# jayday_fez40_5v.net
KiCad netlist of a schematic drawn in EAGLE
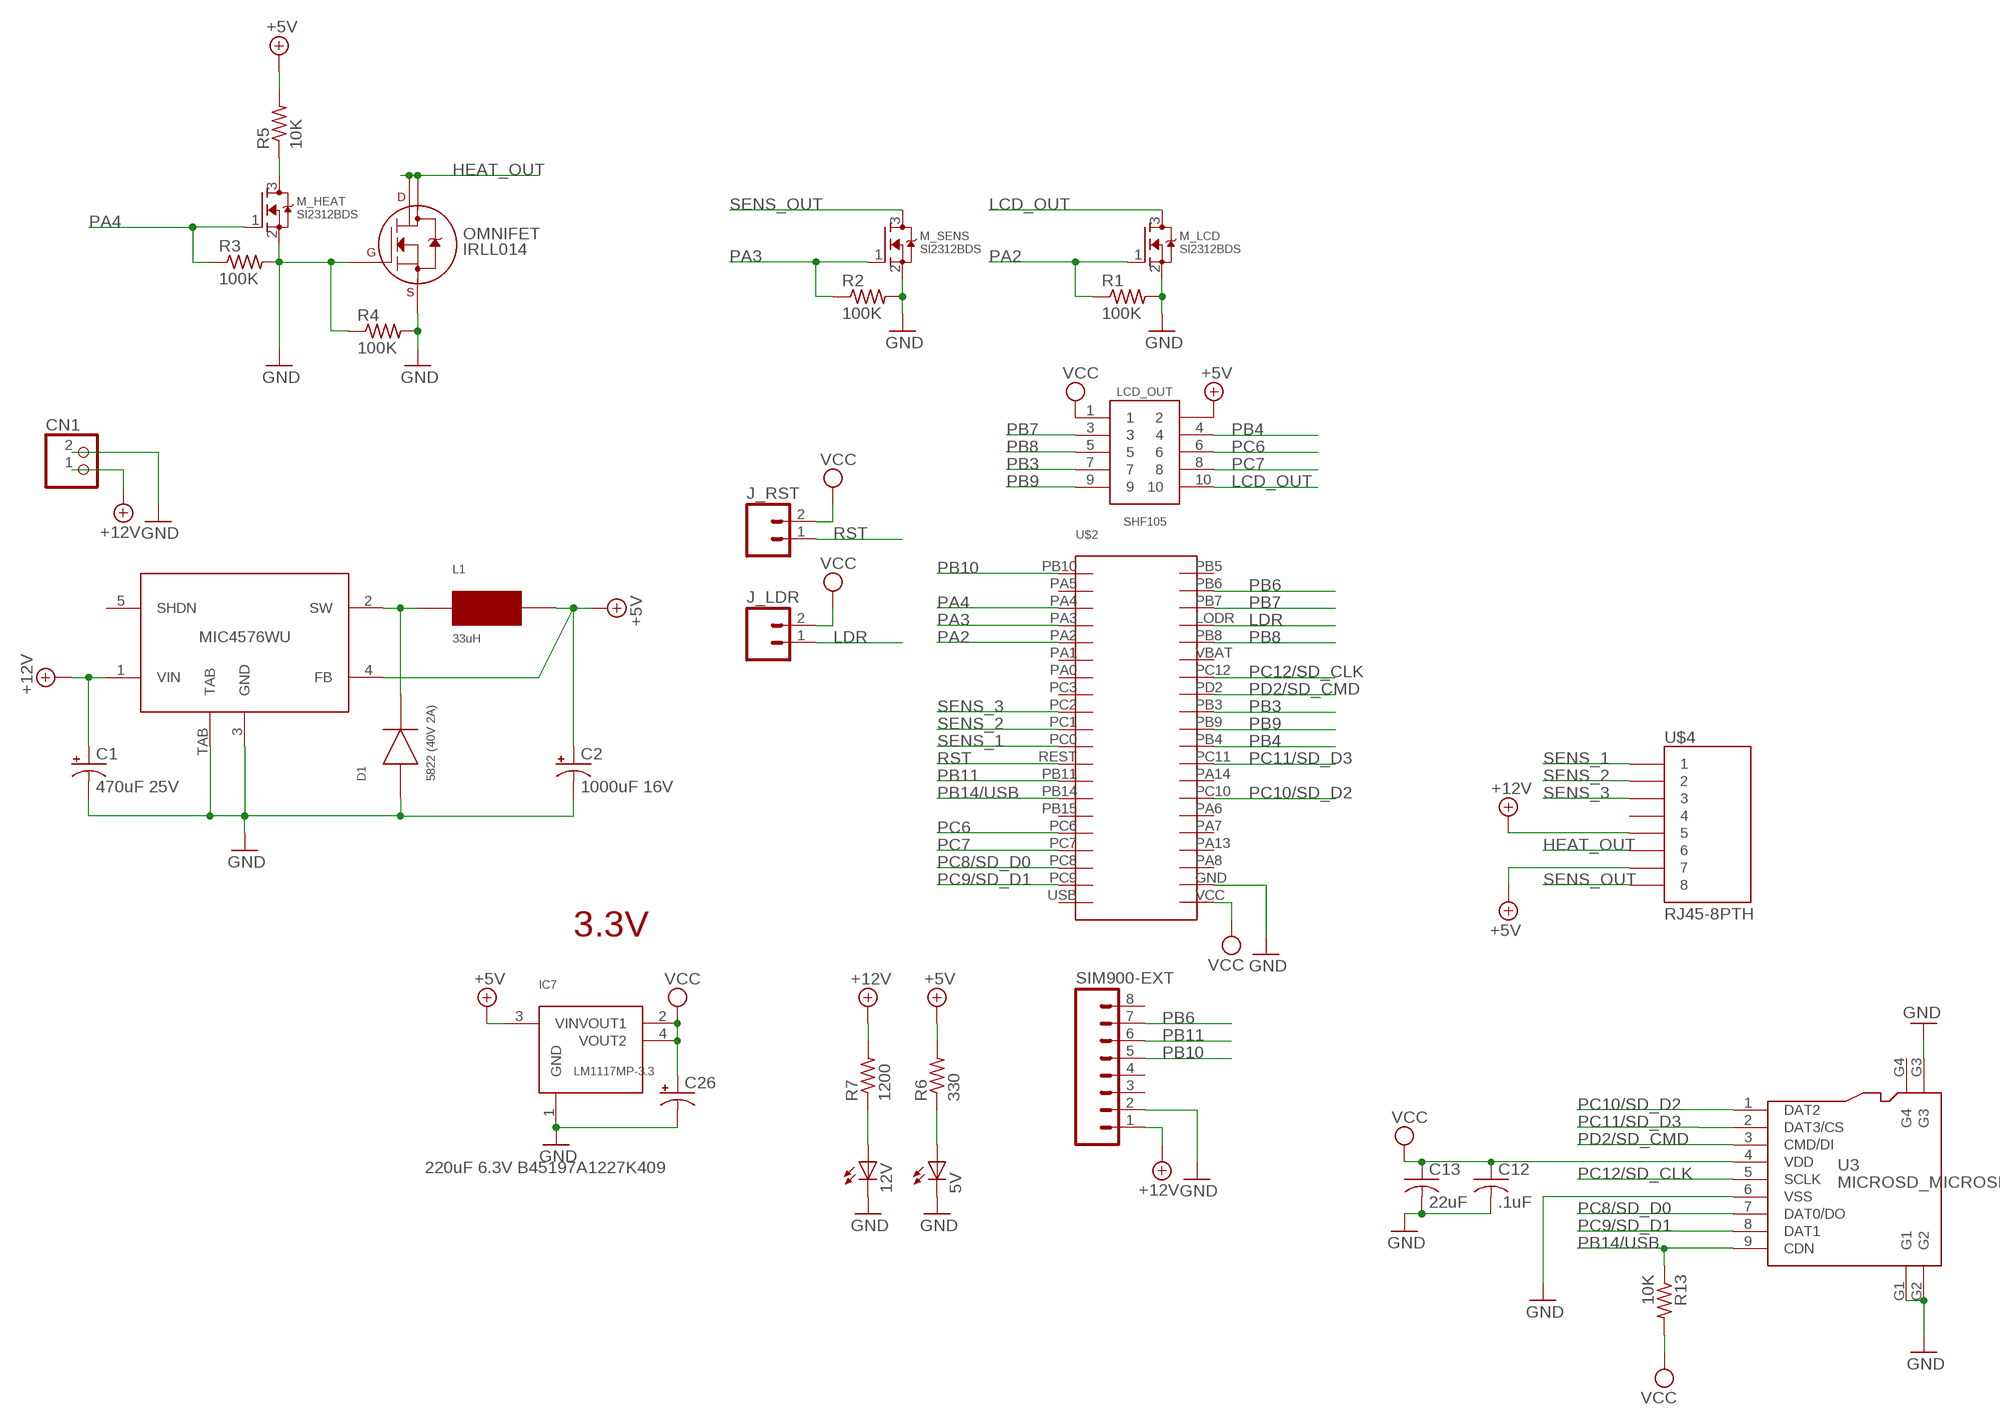
[diagram p0: schematic, sheet 1]

(export (version "E")
  (design (tool "Eeschema 10.0.6"))
  (components
    (comp (ref "5V")
      (value "LEDCHIPLED_0805")
      (footprint "eagle-import:CHIPLED_0805")
      (libsource (lib "eagle-import") (part "LEDCHIPLED_0805"))
    )
    (comp (ref "12V")
      (value "LEDCHIPLED_0805")
      (footprint "eagle-import:CHIPLED_0805")
      (libsource (lib "eagle-import") (part "LEDCHIPLED_0805"))
    )
    (comp (ref "C1")
      (value "470uF 25V")
      (footprint "eagle-import:PANASONIC_E")
      (libsource (lib "eagle-import") (part "CAP_POLE"))
    )
    (comp (ref "C2")
      (value "1000uF 16V")
      (footprint "eagle-import:PANASONIC_E")
      (libsource (lib "eagle-import") (part "CAP_POLE"))
    )
    (comp (ref "C12")
      (value ".1uF")
      (footprint "eagle-import:C0603K")
      (libsource (lib "eagle-import") (part "C-USC0603K"))
    )
    (comp (ref "C13")
      (value "22uF")
      (footprint "eagle-import:C0805K")
      (libsource (lib "eagle-import") (part "C-USC0805K"))
    )
    (comp (ref "C26")
      (value "220uF 6.3V B45197A1227K409")
      (footprint "eagle-import:D_7343-31W")
      (libsource (lib "eagle-import") (part "CPOL-USD/7343-31W"))
    )
    (comp (ref "CN1")
      (value "JST_2PIN-THM-RA")
      (footprint "eagle-import:JST-PH-2-THM-RA")
      (libsource (lib "eagle-import") (part "JST_2PIN-THM-RA"))
    )
    (comp (ref "D1")
      (value "5822 (40V 2A)")
      (footprint "eagle-import:GHI_DIODE_SMA")
      (libsource (lib "eagle-import") (part "GHI_DIODE_SMA"))
    )
    (comp (ref "IC7")
      (value "LM1117MP-3.3")
      (footprint "eagle-import:SOT223")
      (libsource (lib "eagle-import") (part "LM1117"))
    )
    (comp (ref "J_LDR")
      (value "M02PTH")
      (footprint "eagle-import:1X02")
      (libsource (lib "eagle-import") (part "M02PTH"))
    )
    (comp (ref "J_RST")
      (value "M02PTH")
      (footprint "eagle-import:1X02")
      (libsource (lib "eagle-import") (part "M02PTH"))
    )
    (comp (ref "L1")
      (value "33uH")
      (footprint "eagle-import:GHI_UP2BXXX")
      (libsource (lib "eagle-import") (part "GHI_UP2BXXX"))
    )
    (comp (ref "LCD_OUT")
      (value "SHF105")
      (footprint "eagle-import:GAD_PAC_SMD")
      (libsource (lib "eagle-import") (part "SHF105"))
    )
    (comp (ref "M_HEAT")
      (value "SI2312BDS")
      (footprint "eagle-import:TO-236")
      (libsource (lib "eagle-import") (part "SI2312BDS"))
    )
    (comp (ref "M_LCD")
      (value "SI2312BDS")
      (footprint "eagle-import:TO-236")
      (libsource (lib "eagle-import") (part "SI2312BDS"))
    )
    (comp (ref "M_SENS")
      (value "SI2312BDS")
      (footprint "eagle-import:TO-236")
      (libsource (lib "eagle-import") (part "SI2312BDS"))
    )
    (comp (ref "OMNIFET")
      (value "IRLL014")
      (footprint "eagle-import:SOT-223")
      (libsource (lib "eagle-import") (part "IRLL014"))
    )
    (comp (ref "R1")
      (value "100K")
      (footprint "eagle-import:R0603")
      (libsource (lib "eagle-import") (part "R-US_R0603"))
    )
    (comp (ref "R2")
      (value "100K")
      (footprint "eagle-import:R0603")
      (libsource (lib "eagle-import") (part "R-US_R0603"))
    )
    (comp (ref "R3")
      (value "100K")
      (footprint "eagle-import:R0603")
      (libsource (lib "eagle-import") (part "R-US_R0603"))
    )
    (comp (ref "R4")
      (value "100K")
      (footprint "eagle-import:R0603")
      (libsource (lib "eagle-import") (part "R-US_R0603"))
    )
    (comp (ref "R5")
      (value "10K")
      (footprint "eagle-import:R0603")
      (libsource (lib "eagle-import") (part "R-US_R0603"))
    )
    (comp (ref "R6")
      (value "330")
      (footprint "eagle-import:R0603")
      (libsource (lib "eagle-import") (part "rcl_R-US_R0603"))
    )
    (comp (ref "R7")
      (value "1200")
      (footprint "eagle-import:R0603")
      (libsource (lib "eagle-import") (part "rcl_R-US_R0603"))
    )
    (comp (ref "R13")
      (value "10K")
      (footprint "eagle-import:R0603")
      (libsource (lib "eagle-import") (part "rcl_R-US_R0603"))
    )
    (comp (ref "SIM900-EXT")
      (value "M081X08")
      (footprint "eagle-import:1X08")
      (libsource (lib "eagle-import") (part "M081X08"))
    )
    (comp (ref "U$1")
      (value "MIC4576WU")
      (footprint "eagle-import:TO263-5")
      (libsource (lib "eagle-import") (part "MIC4576WU"))
    )
    (comp (ref "U$2")
      (value "FEZ_CERB_40")
      (footprint "eagle-import:FEZ_CERB_40")
      (libsource (lib "eagle-import") (part "FEZ_CERB_40"))
    )
    (comp (ref "U$4")
      (value "RJ45-8PTH")
      (footprint "eagle-import:RJ45-8")
      (libsource (lib "eagle-import") (part "RJ45-8PTH"))
    )
    (comp (ref "U3")
      (value "MICROSD_MICROSD")
      (footprint "eagle-import:MICROSD_MICROSD")
      (libsource (lib "eagle-import") (part "MICROSD_MICROSD"))
    )
  )
  (nets
    (net (code "1") (name "+5V") (class "Default")
      (node (ref "C2") (pin "+") (pinfunction "+_+") (pintype "passive"))
      (node (ref "IC7") (pin "3") (pinfunction "VIN_3") (pintype "bidirectional"))
      (node (ref "L1") (pin "P$2") (pinfunction "2_P$2") (pintype "bidirectional"))
      (node (ref "LCD_OUT") (pin "2") (pinfunction "2_2") (pintype "passive"))
      (node (ref "R5") (pin "2") (pinfunction "2_2") (pintype "passive"))
      (node (ref "R6") (pin "2") (pinfunction "2_2") (pintype "passive"))
      (node (ref "U$1") (pin "4") (pinfunction "FB_4") (pintype "bidirectional"))
      (node (ref "U$4") (pin "7") (pinfunction "7_7") (pintype "bidirectional"))
    )
    (net (code "2") (name "+12V") (class "Default")
      (node (ref "C1") (pin "+") (pinfunction "+_+") (pintype "passive"))
      (node (ref "CN1") (pin "1") (pinfunction "2_1") (pintype "passive"))
      (node (ref "R7") (pin "2") (pinfunction "2_2") (pintype "passive"))
      (node (ref "SIM900-EXT") (pin "1") (pinfunction "1_1") (pintype "passive"))
      (node (ref "U$1") (pin "1") (pinfunction "VIN_1") (pintype "bidirectional"))
      (node (ref "U$4") (pin "5") (pinfunction "5_5") (pintype "bidirectional"))
    )
    (net (code "3") (name "/HEAT_OUT") (class "Default")
      (node (ref "OMNIFET") (pin "2") (pinfunction "D1_2") (pintype "bidirectional"))
      (node (ref "OMNIFET") (pin "4") (pinfunction "D2_4") (pintype "bidirectional"))
      (node (ref "U$4") (pin "6") (pinfunction "6_6") (pintype "bidirectional"))
    )
    (net (code "4") (name "/LCD_OUT") (class "Default")
      (node (ref "LCD_OUT") (pin "10") (pinfunction "10_10") (pintype "passive"))
      (node (ref "M_LCD") (pin "3") (pinfunction "D_3") (pintype "bidirectional"))
    )
    (net (code "5") (name "/LDR") (class "Default")
      (node (ref "J_LDR") (pin "1") (pinfunction "1_1") (pintype "passive"))
      (node (ref "U$2") (pin "LODR") (pinfunction "LODR_LODR") (pintype "bidirectional"))
    )
    (net (code "6") (name "/PA2") (class "Default")
      (node (ref "M_LCD") (pin "1") (pinfunction "G_1") (pintype "bidirectional"))
      (node (ref "R1") (pin "1") (pinfunction "1_1") (pintype "passive"))
      (node (ref "U$2") (pin "PA2") (pinfunction "PA2_PA2") (pintype "bidirectional"))
    )
    (net (code "7") (name "/PA3") (class "Default")
      (node (ref "M_SENS") (pin "1") (pinfunction "G_1") (pintype "bidirectional"))
      (node (ref "R2") (pin "1") (pinfunction "1_1") (pintype "passive"))
      (node (ref "U$2") (pin "PA3") (pinfunction "PA3_PA3") (pintype "bidirectional"))
    )
    (net (code "8") (name "/PA4") (class "Default")
      (node (ref "M_HEAT") (pin "1") (pinfunction "G_1") (pintype "bidirectional"))
      (node (ref "R3") (pin "1") (pinfunction "1_1") (pintype "passive"))
      (node (ref "U$2") (pin "PA4") (pinfunction "PA4_PA4") (pintype "bidirectional"))
    )
    (net (code "9") (name "/PB3") (class "Default")
      (node (ref "LCD_OUT") (pin "7") (pinfunction "7_7") (pintype "passive"))
      (node (ref "U$2") (pin "PB3") (pinfunction "PB3_PB3") (pintype "bidirectional"))
    )
    (net (code "10") (name "/PB4") (class "Default")
      (node (ref "LCD_OUT") (pin "4") (pinfunction "4_4") (pintype "passive"))
      (node (ref "U$2") (pin "PB4") (pinfunction "PB4_PB4") (pintype "bidirectional"))
    )
    (net (code "11") (name "/PB6") (class "Default")
      (node (ref "SIM900-EXT") (pin "7") (pinfunction "7_7") (pintype "passive"))
      (node (ref "U$2") (pin "PB6") (pinfunction "PB6_PB6") (pintype "bidirectional"))
    )
    (net (code "12") (name "/PB7") (class "Default")
      (node (ref "LCD_OUT") (pin "3") (pinfunction "3_3") (pintype "passive"))
      (node (ref "U$2") (pin "PB7") (pinfunction "PB7_PB7") (pintype "bidirectional"))
    )
    (net (code "13") (name "/PB8") (class "Default")
      (node (ref "LCD_OUT") (pin "5") (pinfunction "5_5") (pintype "passive"))
      (node (ref "U$2") (pin "PB8") (pinfunction "PB8_PB8") (pintype "bidirectional"))
    )
    (net (code "14") (name "/PB9") (class "Default")
      (node (ref "LCD_OUT") (pin "9") (pinfunction "9_9") (pintype "passive"))
      (node (ref "U$2") (pin "PB9") (pinfunction "PB9_PB9") (pintype "bidirectional"))
    )
    (net (code "15") (name "/PB10") (class "Default")
      (node (ref "SIM900-EXT") (pin "5") (pinfunction "5_5") (pintype "passive"))
      (node (ref "U$2") (pin "PB10") (pinfunction "PB10_PB10") (pintype "bidirectional"))
    )
    (net (code "16") (name "/PB11") (class "Default")
      (node (ref "SIM900-EXT") (pin "6") (pinfunction "6_6") (pintype "passive"))
      (node (ref "U$2") (pin "PB11") (pinfunction "PB11_PB11") (pintype "bidirectional"))
    )
    (net (code "17") (name "/PB14{slash}USB") (class "Default")
      (node (ref "R13") (pin "1") (pinfunction "1_1") (pintype "passive"))
      (node (ref "U$2") (pin "PB14") (pinfunction "PB14_PB14") (pintype "bidirectional"))
      (node (ref "U3") (pin "9") (pinfunction "CDN_9") (pintype "bidirectional"))
    )
    (net (code "18") (name "/PC6") (class "Default")
      (node (ref "LCD_OUT") (pin "6") (pinfunction "6_6") (pintype "passive"))
      (node (ref "U$2") (pin "PC6") (pinfunction "PC6_PC6") (pintype "bidirectional"))
    )
    (net (code "19") (name "/PC7") (class "Default")
      (node (ref "LCD_OUT") (pin "8") (pinfunction "8_8") (pintype "passive"))
      (node (ref "U$2") (pin "PC7") (pinfunction "PC7_PC7") (pintype "bidirectional"))
    )
    (net (code "20") (name "/PC8{slash}SD_D0") (class "Default")
      (node (ref "U$2") (pin "PC8") (pinfunction "PC8_PC8") (pintype "bidirectional"))
      (node (ref "U3") (pin "7") (pinfunction "DAT0/DO_7") (pintype "bidirectional"))
    )
    (net (code "21") (name "/PC9{slash}SD_D1") (class "Default")
      (node (ref "U$2") (pin "PC9") (pinfunction "PC9_PC9") (pintype "bidirectional"))
      (node (ref "U3") (pin "8") (pinfunction "DAT1_8") (pintype "bidirectional"))
    )
    (net (code "22") (name "/PC10{slash}SD_D2") (class "Default")
      (node (ref "U$2") (pin "PC10") (pinfunction "PC10_PC10") (pintype "bidirectional"))
      (node (ref "U3") (pin "1") (pinfunction "DAT2_1") (pintype "bidirectional"))
    )
    (net (code "23") (name "/PC11{slash}SD_D3") (class "Default")
      (node (ref "U$2") (pin "PC11") (pinfunction "PC11_PC11") (pintype "bidirectional"))
      (node (ref "U3") (pin "2") (pinfunction "DAT3/CS_2") (pintype "bidirectional"))
    )
    (net (code "24") (name "/PC12{slash}SD_CLK") (class "Default")
      (node (ref "U$2") (pin "PC12") (pinfunction "PC12_PC12") (pintype "bidirectional"))
      (node (ref "U3") (pin "5") (pinfunction "SCLK_5") (pintype "bidirectional"))
    )
    (net (code "25") (name "/PD2{slash}SD_CMD") (class "Default")
      (node (ref "U$2") (pin "PD2") (pinfunction "PD2_PD2") (pintype "bidirectional"))
      (node (ref "U3") (pin "3") (pinfunction "CMD/DI_3") (pintype "bidirectional"))
    )
    (net (code "26") (name "/RST") (class "Default")
      (node (ref "J_RST") (pin "1") (pinfunction "1_1") (pintype "passive"))
      (node (ref "U$2") (pin "REST") (pinfunction "REST_REST") (pintype "bidirectional"))
    )
    (net (code "27") (name "/SENS_1") (class "Default")
      (node (ref "U$2") (pin "PC0") (pinfunction "PC0_PC0") (pintype "bidirectional"))
      (node (ref "U$4") (pin "1") (pinfunction "1_1") (pintype "bidirectional"))
    )
    (net (code "28") (name "/SENS_2") (class "Default")
      (node (ref "U$2") (pin "PC1") (pinfunction "PC1_PC1") (pintype "bidirectional"))
      (node (ref "U$4") (pin "2") (pinfunction "2_2") (pintype "bidirectional"))
    )
    (net (code "29") (name "/SENS_3") (class "Default")
      (node (ref "U$2") (pin "PC2") (pinfunction "PC2_PC2") (pintype "bidirectional"))
      (node (ref "U$4") (pin "3") (pinfunction "3_3") (pintype "bidirectional"))
    )
    (net (code "30") (name "/SENS_OUT") (class "Default")
      (node (ref "M_SENS") (pin "3") (pinfunction "D_3") (pintype "bidirectional"))
      (node (ref "U$4") (pin "8") (pinfunction "8_8") (pintype "bidirectional"))
    )
    (net (code "31") (name "GND") (class "Default")
      (node (ref "12V") (pin "C") (pinfunction "C_C") (pintype "passive"))
      (node (ref "5V") (pin "C") (pinfunction "C_C") (pintype "passive"))
      (node (ref "C1") (pin "-") (pinfunction "-_-") (pintype "passive"))
      (node (ref "C12") (pin "2") (pinfunction "2_2") (pintype "passive"))
      (node (ref "C13") (pin "2") (pinfunction "2_2") (pintype "passive"))
      (node (ref "C2") (pin "-") (pinfunction "-_-") (pintype "passive"))
      (node (ref "C26") (pin "-") (pinfunction "-_-") (pintype "passive"))
      (node (ref "CN1") (pin "2") (pinfunction "1_2") (pintype "passive"))
      (node (ref "D1") (pin "A") (pinfunction "A_A") (pintype "bidirectional"))
      (node (ref "IC7") (pin "1") (pinfunction "GND_1") (pintype "bidirectional"))
      (node (ref "M_HEAT") (pin "2") (pinfunction "S_2") (pintype "bidirectional"))
      (node (ref "M_LCD") (pin "2") (pinfunction "S_2") (pintype "bidirectional"))
      (node (ref "M_SENS") (pin "2") (pinfunction "S_2") (pintype "bidirectional"))
      (node (ref "OMNIFET") (pin "1") (pinfunction "G_1") (pintype "tri_state"))
      (node (ref "OMNIFET") (pin "3") (pinfunction "S_3") (pintype "bidirectional"))
      (node (ref "R1") (pin "2") (pinfunction "2_2") (pintype "passive"))
      (node (ref "R2") (pin "2") (pinfunction "2_2") (pintype "passive"))
      (node (ref "R3") (pin "2") (pinfunction "2_2") (pintype "passive"))
      (node (ref "R4") (pin "1") (pinfunction "1_1") (pintype "passive"))
      (node (ref "R4") (pin "2") (pinfunction "2_2") (pintype "passive"))
      (node (ref "SIM900-EXT") (pin "2") (pinfunction "2_2") (pintype "passive"))
      (node (ref "U$1") (pin "3") (pinfunction "GND_3") (pintype "bidirectional"))
      (node (ref "U$1") (pin "TAB") (pinfunction "TAB_TAB") (pintype "bidirectional"))
      (node (ref "U$2") (pin "GND") (pinfunction "GND_GND") (pintype "bidirectional"))
      (node (ref "U3") (pin "6") (pinfunction "VSS_6") (pintype "bidirectional"))
      (node (ref "U3") (pin "G1") (pinfunction "G1_G1") (pintype "bidirectional"))
      (node (ref "U3") (pin "G2") (pinfunction "G2_G2") (pintype "bidirectional"))
      (node (ref "U3") (pin "G3") (pinfunction "G3_G3") (pintype "bidirectional"))
    )
    (net (code "32") (name "Net-(5V-PadA)") (class "Default")
      (node (ref "5V") (pin "A") (pinfunction "A_A") (pintype "passive"))
      (node (ref "R6") (pin "1") (pinfunction "1_1") (pintype "passive"))
    )
    (net (code "33") (name "Net-(12V-PadA)") (class "Default")
      (node (ref "12V") (pin "A") (pinfunction "A_A") (pintype "passive"))
      (node (ref "R7") (pin "1") (pinfunction "1_1") (pintype "passive"))
    )
    (net (code "34") (name "Net-(L1-1)") (class "Default")
      (node (ref "D1") (pin "K") (pinfunction "K_K") (pintype "bidirectional"))
      (node (ref "L1") (pin "P$1") (pinfunction "1_P$1") (pintype "bidirectional"))
      (node (ref "U$1") (pin "2") (pinfunction "SW_2") (pintype "bidirectional"))
    )
    (net (code "35") (name "Net-(M_HEAT-D)") (class "Default")
      (node (ref "M_HEAT") (pin "3") (pinfunction "D_3") (pintype "bidirectional"))
      (node (ref "R5") (pin "1") (pinfunction "1_1") (pintype "passive"))
    )
    (net (code "36") (name "VCC") (class "Default")
      (node (ref "C12") (pin "1") (pinfunction "1_1") (pintype "passive"))
      (node (ref "C13") (pin "1") (pinfunction "1_1") (pintype "passive"))
      (node (ref "C26") (pin "+") (pinfunction "+_+") (pintype "passive"))
      (node (ref "IC7") (pin "2") (pinfunction "VOUT1_2") (pintype "bidirectional"))
      (node (ref "IC7") (pin "4") (pinfunction "VOUT2_4") (pintype "bidirectional"))
      (node (ref "J_LDR") (pin "2") (pinfunction "2_2") (pintype "passive"))
      (node (ref "J_RST") (pin "2") (pinfunction "2_2") (pintype "passive"))
      (node (ref "LCD_OUT") (pin "1") (pinfunction "1_1") (pintype "passive"))
      (node (ref "R13") (pin "2") (pinfunction "2_2") (pintype "passive"))
      (node (ref "U$2") (pin "VCC") (pinfunction "VCC_VCC") (pintype "bidirectional"))
      (node (ref "U3") (pin "4") (pinfunction "VDD_4") (pintype "bidirectional"))
    )
    (net (code "37") (name "unconnected-(SIM900-EXT-Pad3)") (class "Default")
      (node (ref "SIM900-EXT") (pin "3") (pinfunction "3_3") (pintype "passive"))
    )
    (net (code "38") (name "unconnected-(SIM900-EXT-Pad4)") (class "Default")
      (node (ref "SIM900-EXT") (pin "4") (pinfunction "4_4") (pintype "passive"))
    )
    (net (code "39") (name "unconnected-(SIM900-EXT-Pad8)") (class "Default")
      (node (ref "SIM900-EXT") (pin "8") (pinfunction "8_8") (pintype "passive"))
    )
    (net (code "40") (name "unconnected-(U$1-SHDN-Pad5)") (class "Default")
      (node (ref "U$1") (pin "5") (pinfunction "SHDN_5") (pintype "bidirectional"))
    )
    (net (code "41") (name "unconnected-(U$2-PadPA0)") (class "Default")
      (node (ref "U$2") (pin "PA0") (pinfunction "PA0_PA0") (pintype "bidirectional"))
    )
    (net (code "42") (name "unconnected-(U$2-PadPA1)") (class "Default")
      (node (ref "U$2") (pin "PA1") (pinfunction "PA1_PA1") (pintype "bidirectional"))
    )
    (net (code "43") (name "unconnected-(U$2-PadPA5)") (class "Default")
      (node (ref "U$2") (pin "PA5") (pinfunction "PA5_PA5") (pintype "bidirectional"))
    )
    (net (code "44") (name "unconnected-(U$2-PadPA6)") (class "Default")
      (node (ref "U$2") (pin "PA6") (pinfunction "PA6_PA6") (pintype "bidirectional"))
    )
    (net (code "45") (name "unconnected-(U$2-PadPA7)") (class "Default")
      (node (ref "U$2") (pin "PA7") (pinfunction "PA7_PA7") (pintype "bidirectional"))
    )
    (net (code "46") (name "unconnected-(U$2-PadPA8)") (class "Default")
      (node (ref "U$2") (pin "PA8") (pinfunction "PA8_PA8") (pintype "bidirectional"))
    )
    (net (code "47") (name "unconnected-(U$2-PadPA13)") (class "Default")
      (node (ref "U$2") (pin "PA13") (pinfunction "PA13_PA13") (pintype "bidirectional"))
    )
    (net (code "48") (name "unconnected-(U$2-PadPA14)") (class "Default")
      (node (ref "U$2") (pin "PA14") (pinfunction "PA14_PA14") (pintype "bidirectional"))
    )
    (net (code "49") (name "unconnected-(U$2-PadPB5)") (class "Default")
      (node (ref "U$2") (pin "PB5") (pinfunction "PB5_PB5") (pintype "bidirectional"))
    )
    (net (code "50") (name "unconnected-(U$2-PadPB15)") (class "Default")
      (node (ref "U$2") (pin "PB15") (pinfunction "PB15_PB15") (pintype "bidirectional"))
    )
    (net (code "51") (name "unconnected-(U$2-PadPC3)") (class "Default")
      (node (ref "U$2") (pin "PC3") (pinfunction "PC3_PC3") (pintype "bidirectional"))
    )
    (net (code "52") (name "unconnected-(U$2-PadUSB)") (class "Default")
      (node (ref "U$2") (pin "USB") (pinfunction "USB_USB") (pintype "bidirectional"))
    )
    (net (code "53") (name "unconnected-(U$2-PadVBAT)") (class "Default")
      (node (ref "U$2") (pin "VBAT") (pinfunction "VBAT_VBAT") (pintype "bidirectional"))
    )
    (net (code "54") (name "unconnected-(U$4-Pad4)") (class "Default")
      (node (ref "U$4") (pin "4") (pinfunction "4_4") (pintype "bidirectional"))
    )
    (net (code "55") (name "unconnected-(U3-PadG4)") (class "Default")
      (node (ref "U3") (pin "G4") (pinfunction "G4_G4") (pintype "bidirectional"))
    )
  )
)
